# Sonar-Three-Amp-Block.net
KiCad netlist of a schematic drawn in EAGLE
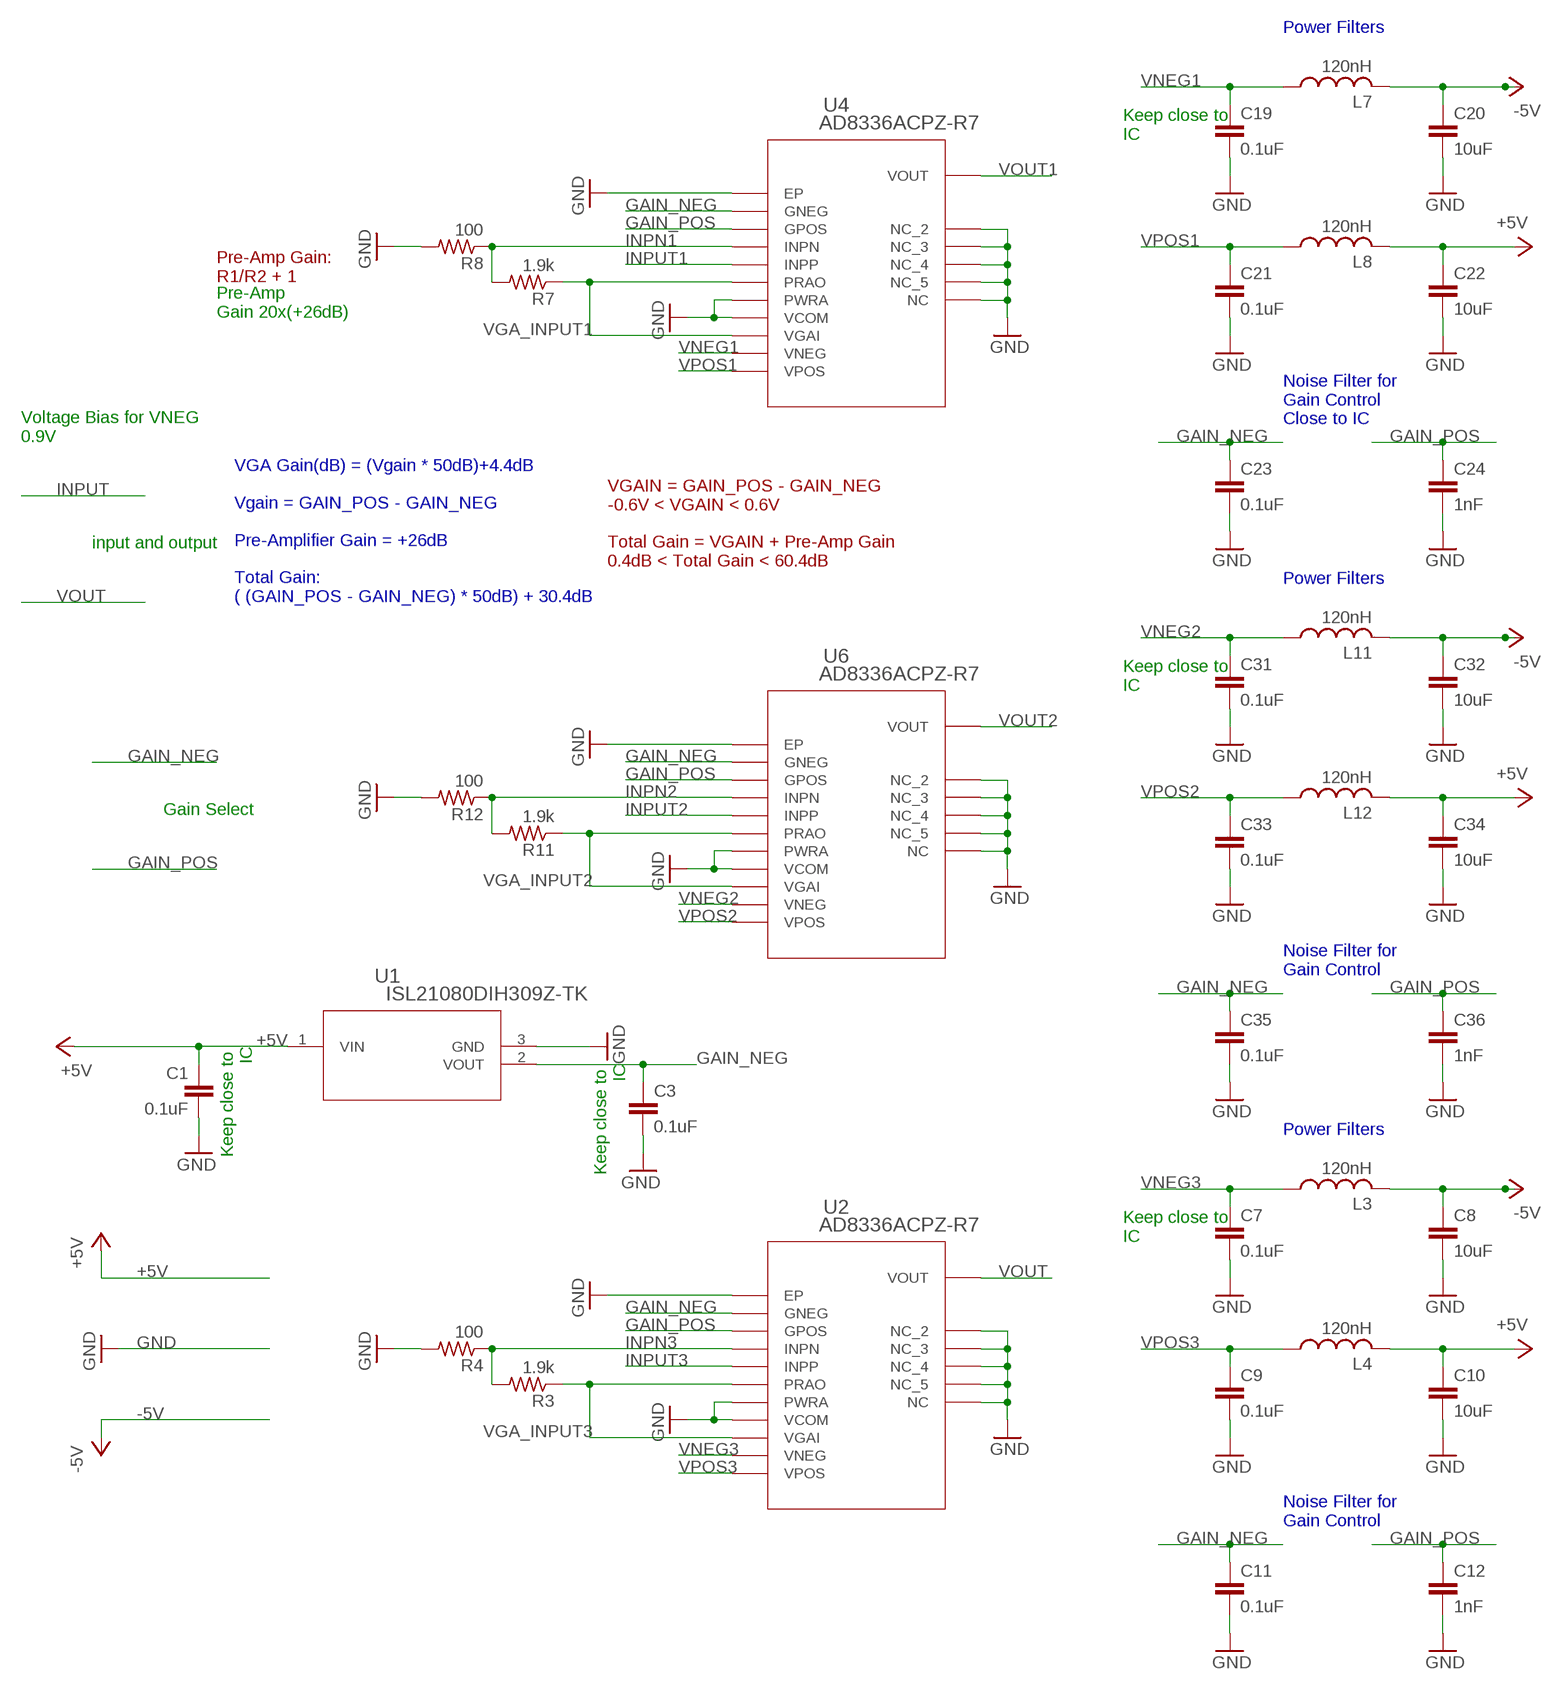
[diagram p0: schematic, sheet 1]

(export (version "E")
  (design (tool "Eeschema 10.0.6"))
  (components
    (comp (ref "C1")
      (value "0.1uF")
      (footprint "eagle-import:C0603")
      (libsource (lib "eagle-import") (part "C-EUC0603"))
    )
    (comp (ref "C3")
      (value "0.1uF")
      (footprint "eagle-import:C0603")
      (libsource (lib "eagle-import") (part "C-EUC0603"))
    )
    (comp (ref "C7")
      (value "0.1uF")
      (footprint "eagle-import:C0603")
      (libsource (lib "eagle-import") (part "C-EUC0603"))
    )
    (comp (ref "C8")
      (value "10uF")
      (footprint "eagle-import:C1206")
      (libsource (lib "eagle-import") (part "resistor_348_C-EUC1206"))
    )
    (comp (ref "C9")
      (value "0.1uF")
      (footprint "eagle-import:C0603")
      (libsource (lib "eagle-import") (part "C-EUC0603"))
    )
    (comp (ref "C10")
      (value "10uF")
      (footprint "eagle-import:C1206")
      (libsource (lib "eagle-import") (part "resistor_348_C-EUC1206"))
    )
    (comp (ref "C11")
      (value "0.1uF")
      (footprint "eagle-import:C0603")
      (libsource (lib "eagle-import") (part "C-EUC0603"))
    )
    (comp (ref "C12")
      (value "1nF")
      (footprint "eagle-import:C0603")
      (libsource (lib "eagle-import") (part "C-EUC0603"))
    )
    (comp (ref "C19")
      (value "0.1uF")
      (footprint "eagle-import:C0603")
      (libsource (lib "eagle-import") (part "C-EUC0603"))
    )
    (comp (ref "C20")
      (value "10uF")
      (footprint "eagle-import:C1206")
      (libsource (lib "eagle-import") (part "resistor_348_C-EUC1206"))
    )
    (comp (ref "C21")
      (value "0.1uF")
      (footprint "eagle-import:C0603")
      (libsource (lib "eagle-import") (part "C-EUC0603"))
    )
    (comp (ref "C22")
      (value "10uF")
      (footprint "eagle-import:C1206")
      (libsource (lib "eagle-import") (part "resistor_348_C-EUC1206"))
    )
    (comp (ref "C23")
      (value "0.1uF")
      (footprint "eagle-import:C0603")
      (libsource (lib "eagle-import") (part "C-EUC0603"))
    )
    (comp (ref "C24")
      (value "1nF")
      (footprint "eagle-import:C0603")
      (libsource (lib "eagle-import") (part "C-EUC0603"))
    )
    (comp (ref "C31")
      (value "0.1uF")
      (footprint "eagle-import:C0603")
      (libsource (lib "eagle-import") (part "C-EUC0603"))
    )
    (comp (ref "C32")
      (value "10uF")
      (footprint "eagle-import:C1206")
      (libsource (lib "eagle-import") (part "resistor_348_C-EUC1206"))
    )
    (comp (ref "C33")
      (value "0.1uF")
      (footprint "eagle-import:C0603")
      (libsource (lib "eagle-import") (part "C-EUC0603"))
    )
    (comp (ref "C34")
      (value "10uF")
      (footprint "eagle-import:C1206")
      (libsource (lib "eagle-import") (part "resistor_348_C-EUC1206"))
    )
    (comp (ref "C35")
      (value "0.1uF")
      (footprint "eagle-import:C0603")
      (libsource (lib "eagle-import") (part "C-EUC0603"))
    )
    (comp (ref "C36")
      (value "1nF")
      (footprint "eagle-import:C0603")
      (libsource (lib "eagle-import") (part "C-EUC0603"))
    )
    (comp (ref "L3")
      (value "120nH")
      (footprint "eagle-import:L3225P")
      (libsource (lib "eagle-import") (part "L-USL3225P"))
    )
    (comp (ref "L4")
      (value "120nH")
      (footprint "eagle-import:L3225P")
      (libsource (lib "eagle-import") (part "L-USL3225P"))
    )
    (comp (ref "L7")
      (value "120nH")
      (footprint "eagle-import:L3225P")
      (libsource (lib "eagle-import") (part "L-USL3225P"))
    )
    (comp (ref "L8")
      (value "120nH")
      (footprint "eagle-import:L3225P")
      (libsource (lib "eagle-import") (part "L-USL3225P"))
    )
    (comp (ref "L11")
      (value "120nH")
      (footprint "eagle-import:L3225P")
      (libsource (lib "eagle-import") (part "L-USL3225P"))
    )
    (comp (ref "L12")
      (value "120nH")
      (footprint "eagle-import:L3225P")
      (libsource (lib "eagle-import") (part "L-USL3225P"))
    )
    (comp (ref "R3")
      (value "1.9k")
      (footprint "eagle-import:R0603")
      (libsource (lib "eagle-import") (part "R-US_R0603"))
    )
    (comp (ref "R4")
      (value "100")
      (footprint "eagle-import:R0603")
      (libsource (lib "eagle-import") (part "R-US_R0603"))
    )
    (comp (ref "R7")
      (value "1.9k")
      (footprint "eagle-import:R0603")
      (libsource (lib "eagle-import") (part "R-US_R0603"))
    )
    (comp (ref "R8")
      (value "100")
      (footprint "eagle-import:R0603")
      (libsource (lib "eagle-import") (part "R-US_R0603"))
    )
    (comp (ref "R11")
      (value "1.9k")
      (footprint "eagle-import:R0603")
      (libsource (lib "eagle-import") (part "R-US_R0603"))
    )
    (comp (ref "R12")
      (value "100")
      (footprint "eagle-import:R0603")
      (libsource (lib "eagle-import") (part "R-US_R0603"))
    )
    (comp (ref "U1")
      (value "ISL21080DIH309Z-TK")
      (footprint "eagle-import:P3_064")
      (fields (field (name "MANUFACTURER_PART_NUMBER") "ISL21080DIH309ZTK"))
      (libsource (lib "eagle-import") (part "ISL21080DIH309Z-TK"))
    )
    (comp (ref "U2")
      (value "AD8336ACPZ-R7")
      (footprint "eagle-import:CP_16_4")
      (fields (field (name "MANUFACTURER_PART_NUMBER") "AD8336ACPZR7"))
      (libsource (lib "eagle-import") (part "AD8336ACPZ-R7"))
    )
    (comp (ref "U4")
      (value "AD8336ACPZ-R7")
      (footprint "eagle-import:CP_16_4")
      (fields (field (name "MANUFACTURER_PART_NUMBER") "AD8336ACPZR7"))
      (libsource (lib "eagle-import") (part "AD8336ACPZ-R7"))
    )
    (comp (ref "U6")
      (value "AD8336ACPZ-R7")
      (footprint "eagle-import:CP_16_4")
      (fields (field (name "MANUFACTURER_PART_NUMBER") "AD8336ACPZR7"))
      (libsource (lib "eagle-import") (part "AD8336ACPZ-R7"))
    )
  )
  (nets
    (net (code "1") (name "+5V") (class "Default")
      (node (ref "C1") (pin "1") (pinfunction "1_1") (pintype "passive"))
      (node (ref "C10") (pin "1") (pinfunction "1_1") (pintype "passive"))
      (node (ref "C22") (pin "1") (pinfunction "1_1") (pintype "passive"))
      (node (ref "C34") (pin "1") (pinfunction "1_1") (pintype "passive"))
      (node (ref "L12") (pin "2") (pinfunction "2_2") (pintype "passive"))
      (node (ref "L4") (pin "2") (pinfunction "2_2") (pintype "passive"))
      (node (ref "L8") (pin "2") (pinfunction "2_2") (pintype "passive"))
      (node (ref "U1") (pin "1") (pinfunction "VIN_1") (pintype "input"))
    )
    (net (code "2") (name "-5V") (class "Default")
      (node (ref "C20") (pin "1") (pinfunction "1_1") (pintype "passive"))
      (node (ref "C32") (pin "1") (pinfunction "1_1") (pintype "passive"))
      (node (ref "C8") (pin "1") (pinfunction "1_1") (pintype "passive"))
      (node (ref "L11") (pin "2") (pinfunction "2_2") (pintype "passive"))
      (node (ref "L3") (pin "2") (pinfunction "2_2") (pintype "passive"))
      (node (ref "L7") (pin "2") (pinfunction "2_2") (pintype "passive"))
    )
    (net (code "3") (name "/GAIN_NEG") (class "Default")
      (node (ref "C11") (pin "1") (pinfunction "1_1") (pintype "passive"))
      (node (ref "C23") (pin "1") (pinfunction "1_1") (pintype "passive"))
      (node (ref "C3") (pin "1") (pinfunction "1_1") (pintype "passive"))
      (node (ref "C35") (pin "1") (pinfunction "1_1") (pintype "passive"))
      (node (ref "U1") (pin "2") (pinfunction "VOUT_2") (pintype "output"))
      (node (ref "U2") (pin "GNEG") (pinfunction "GNEG_GNEG") (pintype "passive"))
      (node (ref "U4") (pin "GNEG") (pinfunction "GNEG_GNEG") (pintype "passive"))
      (node (ref "U6") (pin "GNEG") (pinfunction "GNEG_GNEG") (pintype "passive"))
    )
    (net (code "4") (name "/GAIN_POS") (class "Default")
      (node (ref "C12") (pin "1") (pinfunction "1_1") (pintype "passive"))
      (node (ref "C24") (pin "1") (pinfunction "1_1") (pintype "passive"))
      (node (ref "C36") (pin "1") (pinfunction "1_1") (pintype "passive"))
      (node (ref "U2") (pin "GPOS") (pinfunction "GPOS_GPOS") (pintype "passive"))
      (node (ref "U4") (pin "GPOS") (pinfunction "GPOS_GPOS") (pintype "passive"))
      (node (ref "U6") (pin "GPOS") (pinfunction "GPOS_GPOS") (pintype "passive"))
    )
    (net (code "5") (name "/INPN1") (class "Default")
      (node (ref "R7") (pin "2") (pinfunction "2_2") (pintype "passive"))
      (node (ref "R8") (pin "1") (pinfunction "1_1") (pintype "passive"))
      (node (ref "U4") (pin "INPN") (pinfunction "INPN_INPN") (pintype "passive"))
    )
    (net (code "6") (name "/INPN2") (class "Default")
      (node (ref "R11") (pin "2") (pinfunction "2_2") (pintype "passive"))
      (node (ref "R12") (pin "1") (pinfunction "1_1") (pintype "passive"))
      (node (ref "U6") (pin "INPN") (pinfunction "INPN_INPN") (pintype "passive"))
    )
    (net (code "7") (name "/INPN3") (class "Default")
      (node (ref "R3") (pin "2") (pinfunction "2_2") (pintype "passive"))
      (node (ref "R4") (pin "1") (pinfunction "1_1") (pintype "passive"))
      (node (ref "U2") (pin "INPN") (pinfunction "INPN_INPN") (pintype "passive"))
    )
    (net (code "9") (name "/INPUT1") (class "Default")
      (node (ref "U4") (pin "INPP") (pinfunction "INPP_INPP") (pintype "passive"))
    )
    (net (code "10") (name "/INPUT2") (class "Default")
      (node (ref "U6") (pin "INPP") (pinfunction "INPP_INPP") (pintype "passive"))
    )
    (net (code "11") (name "/INPUT3") (class "Default")
      (node (ref "U2") (pin "INPP") (pinfunction "INPP_INPP") (pintype "passive"))
    )
    (net (code "12") (name "/VGA_INPUT1") (class "Default")
      (node (ref "R7") (pin "1") (pinfunction "1_1") (pintype "passive"))
      (node (ref "U4") (pin "PRAO") (pinfunction "PRAO_PRAO") (pintype "passive"))
      (node (ref "U4") (pin "VGAI") (pinfunction "VGAI_VGAI") (pintype "passive"))
    )
    (net (code "13") (name "/VGA_INPUT2") (class "Default")
      (node (ref "R11") (pin "1") (pinfunction "1_1") (pintype "passive"))
      (node (ref "U6") (pin "PRAO") (pinfunction "PRAO_PRAO") (pintype "passive"))
      (node (ref "U6") (pin "VGAI") (pinfunction "VGAI_VGAI") (pintype "passive"))
    )
    (net (code "14") (name "/VGA_INPUT3") (class "Default")
      (node (ref "R3") (pin "1") (pinfunction "1_1") (pintype "passive"))
      (node (ref "U2") (pin "PRAO") (pinfunction "PRAO_PRAO") (pintype "passive"))
      (node (ref "U2") (pin "VGAI") (pinfunction "VGAI_VGAI") (pintype "passive"))
    )
    (net (code "15") (name "/VNEG1") (class "Default")
      (node (ref "C19") (pin "1") (pinfunction "1_1") (pintype "passive"))
      (node (ref "L7") (pin "1") (pinfunction "1_1") (pintype "passive"))
      (node (ref "U4") (pin "VNEG") (pinfunction "VNEG_VNEG") (pintype "passive"))
    )
    (net (code "16") (name "/VNEG2") (class "Default")
      (node (ref "C31") (pin "1") (pinfunction "1_1") (pintype "passive"))
      (node (ref "L11") (pin "1") (pinfunction "1_1") (pintype "passive"))
      (node (ref "U6") (pin "VNEG") (pinfunction "VNEG_VNEG") (pintype "passive"))
    )
    (net (code "17") (name "/VNEG3") (class "Default")
      (node (ref "C7") (pin "1") (pinfunction "1_1") (pintype "passive"))
      (node (ref "L3") (pin "1") (pinfunction "1_1") (pintype "passive"))
      (node (ref "U2") (pin "VNEG") (pinfunction "VNEG_VNEG") (pintype "passive"))
    )
    (net (code "18") (name "/VOUT") (class "Default")
      (node (ref "U2") (pin "VOUT") (pinfunction "VOUT_VOUT") (pintype "passive"))
    )
    (net (code "19") (name "/VOUT1") (class "Default")
      (node (ref "U4") (pin "VOUT") (pinfunction "VOUT_VOUT") (pintype "passive"))
    )
    (net (code "20") (name "/VOUT2") (class "Default")
      (node (ref "U6") (pin "VOUT") (pinfunction "VOUT_VOUT") (pintype "passive"))
    )
    (net (code "21") (name "/VPOS1") (class "Default")
      (node (ref "C21") (pin "1") (pinfunction "1_1") (pintype "passive"))
      (node (ref "L8") (pin "1") (pinfunction "1_1") (pintype "passive"))
      (node (ref "U4") (pin "VPOS") (pinfunction "VPOS_VPOS") (pintype "passive"))
    )
    (net (code "22") (name "/VPOS2") (class "Default")
      (node (ref "C33") (pin "1") (pinfunction "1_1") (pintype "passive"))
      (node (ref "L12") (pin "1") (pinfunction "1_1") (pintype "passive"))
      (node (ref "U6") (pin "VPOS") (pinfunction "VPOS_VPOS") (pintype "passive"))
    )
    (net (code "23") (name "/VPOS3") (class "Default")
      (node (ref "C9") (pin "1") (pinfunction "1_1") (pintype "passive"))
      (node (ref "L4") (pin "1") (pinfunction "1_1") (pintype "passive"))
      (node (ref "U2") (pin "VPOS") (pinfunction "VPOS_VPOS") (pintype "passive"))
    )
    (net (code "24") (name "GND") (class "Default")
      (node (ref "C1") (pin "2") (pinfunction "2_2") (pintype "passive"))
      (node (ref "C10") (pin "2") (pinfunction "2_2") (pintype "passive"))
      (node (ref "C11") (pin "2") (pinfunction "2_2") (pintype "passive"))
      (node (ref "C12") (pin "2") (pinfunction "2_2") (pintype "passive"))
      (node (ref "C19") (pin "2") (pinfunction "2_2") (pintype "passive"))
      (node (ref "C20") (pin "2") (pinfunction "2_2") (pintype "passive"))
      (node (ref "C21") (pin "2") (pinfunction "2_2") (pintype "passive"))
      (node (ref "C22") (pin "2") (pinfunction "2_2") (pintype "passive"))
      (node (ref "C23") (pin "2") (pinfunction "2_2") (pintype "passive"))
      (node (ref "C24") (pin "2") (pinfunction "2_2") (pintype "passive"))
      (node (ref "C3") (pin "2") (pinfunction "2_2") (pintype "passive"))
      (node (ref "C31") (pin "2") (pinfunction "2_2") (pintype "passive"))
      (node (ref "C32") (pin "2") (pinfunction "2_2") (pintype "passive"))
      (node (ref "C33") (pin "2") (pinfunction "2_2") (pintype "passive"))
      (node (ref "C34") (pin "2") (pinfunction "2_2") (pintype "passive"))
      (node (ref "C35") (pin "2") (pinfunction "2_2") (pintype "passive"))
      (node (ref "C36") (pin "2") (pinfunction "2_2") (pintype "passive"))
      (node (ref "C7") (pin "2") (pinfunction "2_2") (pintype "passive"))
      (node (ref "C8") (pin "2") (pinfunction "2_2") (pintype "passive"))
      (node (ref "C9") (pin "2") (pinfunction "2_2") (pintype "passive"))
      (node (ref "R12") (pin "2") (pinfunction "2_2") (pintype "passive"))
      (node (ref "R4") (pin "2") (pinfunction "2_2") (pintype "passive"))
      (node (ref "R8") (pin "2") (pinfunction "2_2") (pintype "passive"))
      (node (ref "U1") (pin "3") (pinfunction "GND_3") (pintype "power_in"))
      (node (ref "U2") (pin "GND1") (pinfunction "EP_GND1") (pintype "passive"))
      (node (ref "U2") (pin "NC") (pinfunction "NC_NC") (pintype "passive"))
      (node (ref "U2") (pin "NC1") (pinfunction "NC_2_NC1") (pintype "passive"))
      (node (ref "U2") (pin "NC2") (pinfunction "NC_3_NC2") (pintype "passive"))
      (node (ref "U2") (pin "NC3") (pinfunction "NC_4_NC3") (pintype "passive"))
      (node (ref "U2") (pin "NC4") (pinfunction "NC_5_NC4") (pintype "passive"))
      (node (ref "U2") (pin "PWRA") (pinfunction "PWRA_PWRA") (pintype "passive"))
      (node (ref "U2") (pin "VCOM") (pinfunction "VCOM_VCOM") (pintype "passive"))
      (node (ref "U4") (pin "GND1") (pinfunction "EP_GND1") (pintype "passive"))
      (node (ref "U4") (pin "NC") (pinfunction "NC_NC") (pintype "passive"))
      (node (ref "U4") (pin "NC1") (pinfunction "NC_2_NC1") (pintype "passive"))
      (node (ref "U4") (pin "NC2") (pinfunction "NC_3_NC2") (pintype "passive"))
      (node (ref "U4") (pin "NC3") (pinfunction "NC_4_NC3") (pintype "passive"))
      (node (ref "U4") (pin "NC4") (pinfunction "NC_5_NC4") (pintype "passive"))
      (node (ref "U4") (pin "PWRA") (pinfunction "PWRA_PWRA") (pintype "passive"))
      (node (ref "U4") (pin "VCOM") (pinfunction "VCOM_VCOM") (pintype "passive"))
      (node (ref "U6") (pin "GND1") (pinfunction "EP_GND1") (pintype "passive"))
      (node (ref "U6") (pin "NC") (pinfunction "NC_NC") (pintype "passive"))
      (node (ref "U6") (pin "NC1") (pinfunction "NC_2_NC1") (pintype "passive"))
      (node (ref "U6") (pin "NC2") (pinfunction "NC_3_NC2") (pintype "passive"))
      (node (ref "U6") (pin "NC3") (pinfunction "NC_4_NC3") (pintype "passive"))
      (node (ref "U6") (pin "NC4") (pinfunction "NC_5_NC4") (pintype "passive"))
      (node (ref "U6") (pin "PWRA") (pinfunction "PWRA_PWRA") (pintype "passive"))
      (node (ref "U6") (pin "VCOM") (pinfunction "VCOM_VCOM") (pintype "passive"))
    )
  )
)
